# I2C.net
KiCad netlist of a schematic drawn in Altium Designer
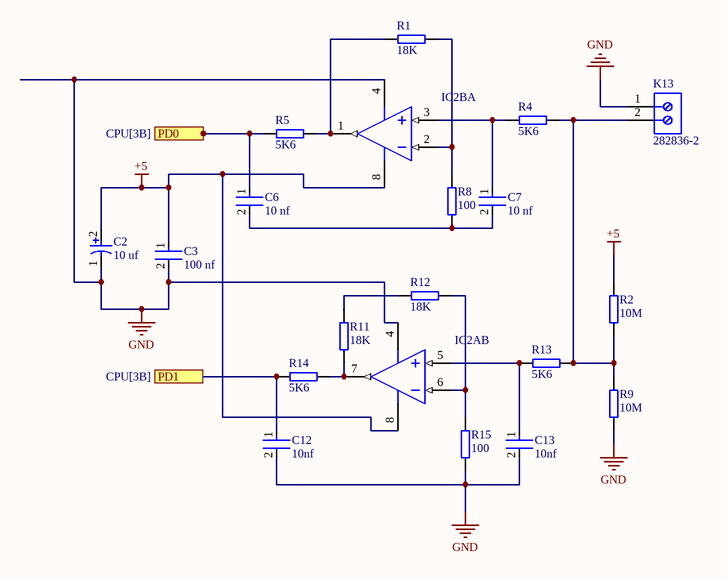
[diagram p0: I2C.SchDoc]

(export (version "E")
  (design (tool "Eeschema 10.0.6"))
  (components
    (comp (ref "C2")
      (value "10 uf")
      (footprint "CE_D8_L10")
      (fields (field (name "MANUFACTURER") "Panasonic"))
      (libsource (lib "Soldeerstation_Final") (part "Capacitor_Electrolytic"))
    )
    (comp (ref "C3")
      (value "100 nf")
      (footprint "CC_0805_L")
      (fields
        (field (name "MANUFACTURER") "KEMET")
        (field (name "OCTOPART") "https://octopart.com/c0805c224k5ractu-kemet-144670")
        (field (name "MANUFACTURER PART NUMBER") "C0805C224K5RACTU")
      )
      (libsource (lib "Soldeerstation_Final") (part "Capacitor_Ceramic"))
    )
    (comp (ref "C6")
      (value "10 nf")
      (footprint "CC_0805_L")
      (fields
        (field (name "MANUFACTURER") "KEMET")
        (field (name "OCTOPART") "https://octopart.com/c0805c224k5ractu-kemet-144670")
        (field (name "MANUFACTURER PART NUMBER") "C0805C224K5RACTU")
      )
      (libsource (lib "Soldeerstation_Final") (part "Capacitor_Ceramic"))
    )
    (comp (ref "C7")
      (value "10 nf")
      (footprint "CC_0805_L")
      (fields
        (field (name "MANUFACTURER") "KEMET")
        (field (name "OCTOPART") "https://octopart.com/c0805c224k5ractu-kemet-144670")
        (field (name "MANUFACTURER PART NUMBER") "C0805C224K5RACTU")
      )
      (libsource (lib "Soldeerstation_Final") (part "Capacitor_Ceramic"))
    )
    (comp (ref "C12")
      (value "10nf")
      (footprint "CC_0805_L")
      (fields
        (field (name "MANUFACTURER") "KEMET")
        (field (name "OCTOPART") "https://octopart.com/c0805c224k5ractu-kemet-144670")
        (field (name "MANUFACTURER PART NUMBER") "C0805C224K5RACTU")
      )
      (libsource (lib "Soldeerstation_Final") (part "Capacitor_Ceramic"))
    )
    (comp (ref "C13")
      (value "10nf")
      (footprint "CC_0805_L")
      (fields
        (field (name "MANUFACTURER") "KEMET")
        (field (name "OCTOPART") "https://octopart.com/c0805c224k5ractu-kemet-144670")
        (field (name "MANUFACTURER PART NUMBER") "C0805C224K5RACTU")
      )
      (libsource (lib "Soldeerstation_Final") (part "Capacitor_Ceramic"))
    )
    (comp (ref "IC2A")
      (value "~")
      (footprint "MSOP_8_M")
      (libsource (lib "Soldeerstation_Final") (part "Dual_Opamp"))
    )
    (comp (ref "IC2B")
      (value "~")
      (footprint "MSOP_8_M")
      (libsource (lib "Soldeerstation_Final") (part "Dual_Opamp"))
    )
    (comp (ref "K13")
      (value "282836-2")
      (footprint "TECO-282836-2_V")
      (description "Female Header, Pitch 5 mm, 1 x 2 Position, Height 10 mm, Tail Length 3.5 mm, Rohs, Bulk")
      (fields (field (name "VOLTAGE") "300V") (field (name "MANUFACTURER") "TE Connectivity"))
      (libsource (lib "Soldeerstation_Final") (part "CMP-1684-00017-1"))
    )
    (comp (ref "R1")
      (value "18K")
      (footprint "0805_M")
      (fields (field (name "MANUFACTURER") "Vishay Dale") (field (name "PART NUMBER") "CRCW08050000Z0EA"))
      (libsource (lib "Soldeerstation_Final") (part "Resistor"))
    )
    (comp (ref "R2")
      (value "10M")
      (footprint "0805_M")
      (fields (field (name "MANUFACTURER") "Vishay Dale") (field (name "PART NUMBER") "CRCW08050000Z0EA"))
      (libsource (lib "Soldeerstation_Final") (part "Resistor"))
    )
    (comp (ref "R4")
      (value "5K6")
      (footprint "0805_M")
      (fields (field (name "MANUFACTURER") "Vishay Dale") (field (name "PART NUMBER") "CRCW08050000Z0EA"))
      (libsource (lib "Soldeerstation_Final") (part "Resistor"))
    )
    (comp (ref "R5")
      (value "5K6")
      (footprint "0805_M")
      (fields (field (name "MANUFACTURER") "Vishay Dale") (field (name "PART NUMBER") "CRCW08050000Z0EA"))
      (libsource (lib "Soldeerstation_Final") (part "Resistor"))
    )
    (comp (ref "R8")
      (value "100")
      (footprint "0805_M")
      (fields (field (name "MANUFACTURER") "Vishay Dale") (field (name "PART NUMBER") "CRCW08050000Z0EA"))
      (libsource (lib "Soldeerstation_Final") (part "Resistor"))
    )
    (comp (ref "R9")
      (value "10M")
      (footprint "0805_M")
      (fields (field (name "MANUFACTURER") "Vishay Dale") (field (name "PART NUMBER") "CRCW08050000Z0EA"))
      (libsource (lib "Soldeerstation_Final") (part "Resistor"))
    )
    (comp (ref "R11")
      (value "18K")
      (footprint "0805_M")
      (fields (field (name "MANUFACTURER") "Vishay Dale") (field (name "PART NUMBER") "CRCW08050000Z0EA"))
      (libsource (lib "Soldeerstation_Final") (part "Resistor"))
    )
    (comp (ref "R12")
      (value "18K")
      (footprint "0805_M")
      (fields (field (name "MANUFACTURER") "Vishay Dale") (field (name "PART NUMBER") "CRCW08050000Z0EA"))
      (libsource (lib "Soldeerstation_Final") (part "Resistor"))
    )
    (comp (ref "R13")
      (value "5K6")
      (footprint "0805_M")
      (fields (field (name "MANUFACTURER") "Vishay Dale") (field (name "PART NUMBER") "CRCW08050000Z0EA"))
      (libsource (lib "Soldeerstation_Final") (part "Resistor"))
    )
    (comp (ref "R14")
      (value "5K6")
      (footprint "0805_M")
      (fields (field (name "MANUFACTURER") "Vishay Dale") (field (name "PART NUMBER") "CRCW08050000Z0EA"))
      (libsource (lib "Soldeerstation_Final") (part "Resistor"))
    )
    (comp (ref "R15")
      (value "100")
      (footprint "0805_M")
      (fields (field (name "MANUFACTURER") "Vishay Dale") (field (name "PART NUMBER") "CRCW08050000Z0EA"))
      (libsource (lib "Soldeerstation_Final") (part "Resistor"))
    )
  )
  (nets
    (net (code "1") (name "+5") (class "Default")
      (node (ref "C2") (pin "2") (pinfunction "2_2") (pintype "passive"))
      (node (ref "C3") (pin "1") (pinfunction "1_1") (pintype "passive"))
      (node (ref "IC2A") (pin "8") (pinfunction "VDD_8") (pintype "power_in"))
      (node (ref "IC2B") (pin "8") (pinfunction "VDD_8") (pintype "power_in"))
      (node (ref "R2") (pin "2") (pinfunction "2_2") (pintype "passive"))
    )
    (net (code "2") (name "/PD0") (class "Default")
      (node (ref "C6") (pin "1") (pinfunction "1_1") (pintype "passive"))
      (node (ref "R5") (pin "1") (pinfunction "1_1") (pintype "passive"))
    )
    (net (code "3") (name "/PD1") (class "Default")
      (node (ref "C12") (pin "1") (pinfunction "1_1") (pintype "passive"))
      (node (ref "R14") (pin "1") (pinfunction "1_1") (pintype "passive"))
    )
    (net (code "4") (name "GND") (class "Default")
      (node (ref "C12") (pin "2") (pinfunction "2_2") (pintype "passive"))
      (node (ref "C13") (pin "2") (pinfunction "2_2") (pintype "passive"))
      (node (ref "C2") (pin "1") (pinfunction "1_1") (pintype "passive"))
      (node (ref "C3") (pin "2") (pinfunction "2_2") (pintype "passive"))
      (node (ref "IC2A") (pin "4") (pinfunction "VSS_4") (pintype "power_in"))
      (node (ref "IC2B") (pin "4") (pinfunction "VSS_4") (pintype "power_in"))
      (node (ref "K13") (pin "1") (pinfunction "1_1") (pintype "passive"))
      (node (ref "R15") (pin "1") (pinfunction "1_1") (pintype "passive"))
      (node (ref "R9") (pin "1") (pinfunction "1_1") (pintype "passive"))
    )
    (net (code "5") (name "Net-(C6-Pad2)") (class "Default")
      (node (ref "C6") (pin "2") (pinfunction "2_2") (pintype "passive"))
      (node (ref "C7") (pin "2") (pinfunction "2_2") (pintype "passive"))
      (node (ref "R8") (pin "1") (pinfunction "1_1") (pintype "passive"))
    )
    (net (code "6") (name "Net-(IC2AB-VINB+)") (class "Default")
      (node (ref "C13") (pin "1") (pinfunction "1_1") (pintype "passive"))
      (node (ref "IC2A") (pin "5") (pinfunction "VINB+_5") (pintype "input"))
      (node (ref "R13") (pin "1") (pinfunction "1_1") (pintype "passive"))
    )
    (net (code "7") (name "Net-(IC2AB-VINB-)") (class "Default")
      (node (ref "IC2A") (pin "6") (pinfunction "VINB-_6") (pintype "input"))
      (node (ref "R12") (pin "2") (pinfunction "2_2") (pintype "passive"))
      (node (ref "R15") (pin "2") (pinfunction "2_2") (pintype "passive"))
    )
    (net (code "8") (name "Net-(IC2AB-VOUTB)") (class "Default")
      (node (ref "IC2A") (pin "7") (pinfunction "VOUTB_7") (pintype "output"))
      (node (ref "R11") (pin "1") (pinfunction "1_1") (pintype "passive"))
      (node (ref "R14") (pin "2") (pinfunction "2_2") (pintype "passive"))
    )
    (net (code "9") (name "Net-(IC2BA-VINA+)") (class "Default")
      (node (ref "C7") (pin "1") (pinfunction "1_1") (pintype "passive"))
      (node (ref "IC2B") (pin "3") (pinfunction "VINA+_3") (pintype "input"))
      (node (ref "R4") (pin "1") (pinfunction "1_1") (pintype "passive"))
    )
    (net (code "10") (name "Net-(IC2BA-VINA-)") (class "Default")
      (node (ref "IC2B") (pin "2") (pinfunction "VINA-_2") (pintype "input"))
      (node (ref "R1") (pin "2") (pinfunction "2_2") (pintype "passive"))
      (node (ref "R8") (pin "2") (pinfunction "2_2") (pintype "passive"))
    )
    (net (code "11") (name "Net-(IC2BA-VOUTA)") (class "Default")
      (node (ref "IC2B") (pin "1") (pinfunction "VOUTA_1") (pintype "output"))
      (node (ref "R1") (pin "1") (pinfunction "1_1") (pintype "passive"))
      (node (ref "R5") (pin "2") (pinfunction "2_2") (pintype "passive"))
    )
    (net (code "12") (name "Net-(K13-Pad2)") (class "Default")
      (node (ref "K13") (pin "2") (pinfunction "2_2") (pintype "passive"))
      (node (ref "R13") (pin "2") (pinfunction "2_2") (pintype "passive"))
      (node (ref "R2") (pin "1") (pinfunction "1_1") (pintype "passive"))
      (node (ref "R4") (pin "2") (pinfunction "2_2") (pintype "passive"))
      (node (ref "R9") (pin "2") (pinfunction "2_2") (pintype "passive"))
    )
    (net (code "13") (name "Net-(R11-Pad2)") (class "Default")
      (node (ref "R11") (pin "2") (pinfunction "2_2") (pintype "passive"))
      (node (ref "R12") (pin "1") (pinfunction "1_1") (pintype "passive"))
    )
  )
)
